# OutputJack.net
KiCad netlist of a schematic drawn in Altium Designer
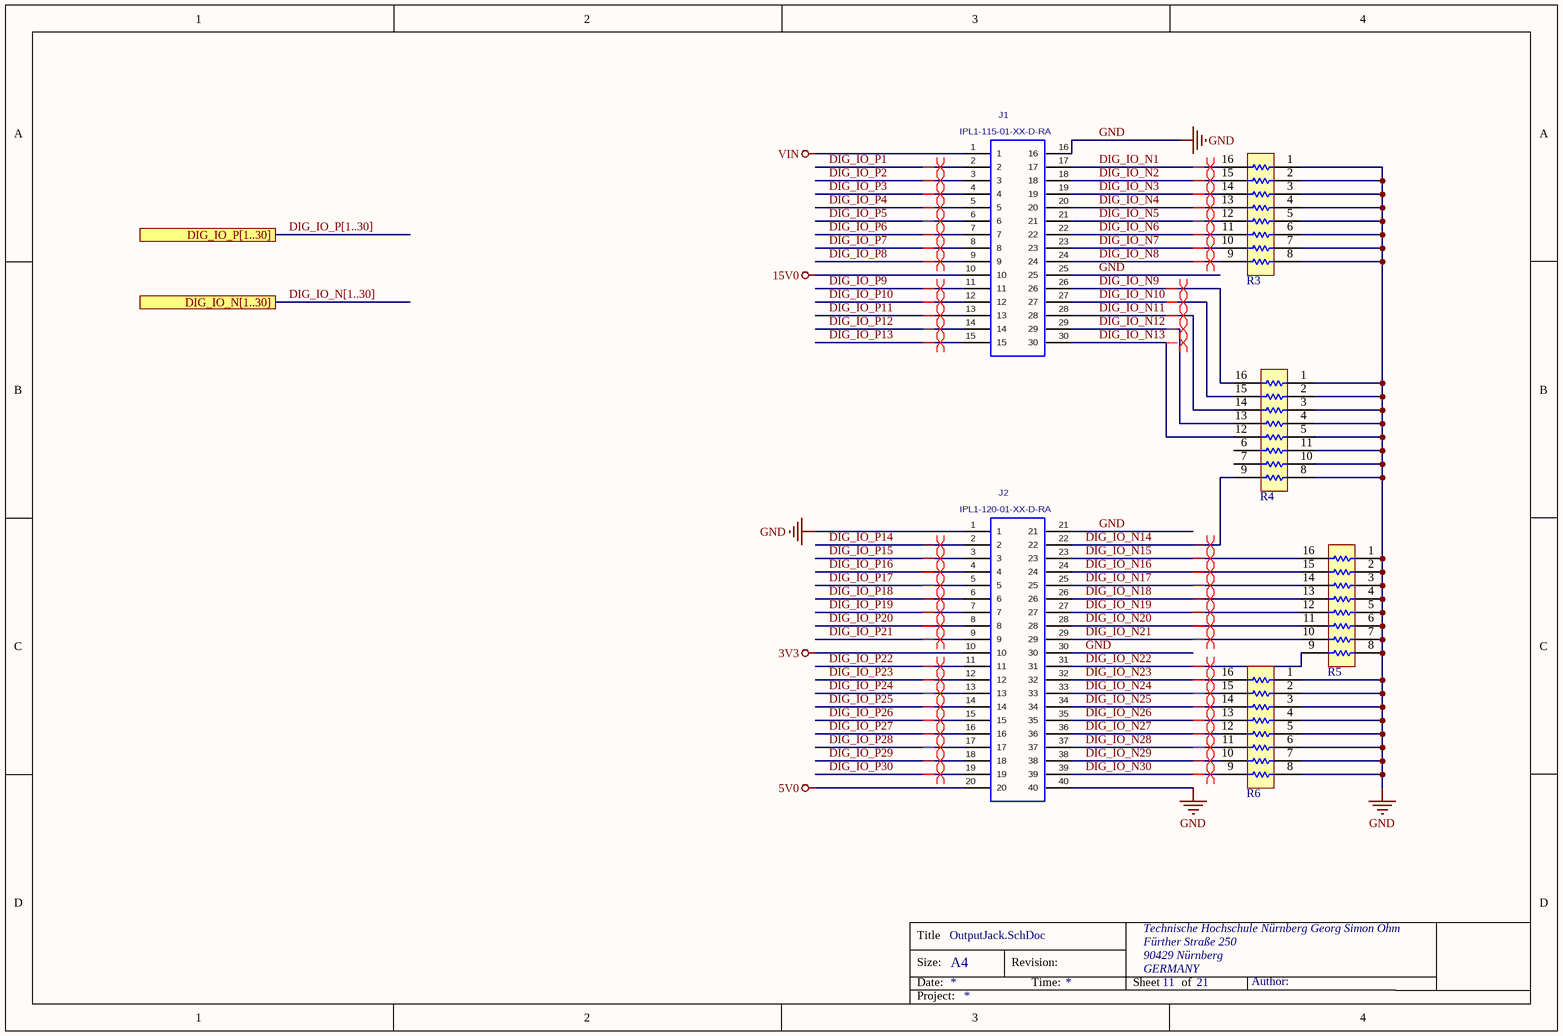
[diagram p0: OutputJack.SchDoc]

(export (version "E")
  (design (tool "Eeschema 10.0.6"))
  (components
    (comp (ref "J1")
      (value "IPL1-115-01-XX-D-RA")
      (footprint "IPL1-115-01-XX-D-RA")
      (description "Terminal Assembly, Double Row, Right Angle, Thru-Hole, 0.100\" x 0.100\" Pitch, 30 Pins.")
      (fields (field (name "CREATED") "2019-12-17_Wendy_Xin"))
      (libsource (lib "connectors") (part "IPL1-115-01-XX-D-RA"))
    )
    (comp (ref "J2")
      (value "IPL1-120-01-XX-D-RA")
      (footprint "IPL1-120-01-XX-D-RA")
      (description "Terminal Assembly, Double Row, Right Angle, Thru-Hole, 0.100\" x 0.100\" Pitch, 40 Pins.")
      (fields (field (name "CREATED") "2019-07-18_Wendy Xin"))
      (libsource (lib "connectors") (part "IPL1-120-01-XX-D-RA"))
    )
    (comp (ref "R3")
      (value "0.063W")
      (footprint "RESCAXE-50P380X160X45-16N")
      (description "Standard thick film resistor array with 8 resistors")
      (fields (field (name "CREATED") "2020-01-03_Thilo_Wendt"))
      (libsource (lib "standard_rlc") (part "8xR-Array_1_part"))
    )
    (comp (ref "R4")
      (value "0.063W")
      (footprint "RESCAXE-50P380X160X45-16N")
      (description "Standard thick film resistor array with 8 resistors")
      (fields (field (name "CREATED") "2020-01-03_Thilo_Wendt"))
      (libsource (lib "") (part "8xR-Array_1_part_1"))
    )
    (comp (ref "R5")
      (value "0.063W")
      (footprint "RESCAXE-50P380X160X45-16N")
      (description "Standard thick film resistor array with 8 resistors")
      (fields (field (name "CREATED") "2020-01-03_Thilo_Wendt"))
      (libsource (lib "standard_rlc") (part "8xR-Array_1_part"))
    )
    (comp (ref "R6")
      (value "0.063W")
      (footprint "RESCAXE-50P380X160X45-16N")
      (description "Standard thick film resistor array with 8 resistors")
      (fields (field (name "CREATED") "2020-01-03_Thilo_Wendt"))
      (libsource (lib "standard_rlc") (part "8xR-Array_1_part"))
    )
  )
  (nets
    (net (code "1") (name "/DIG_IO_N1") (class "Default")
      (node (ref "J1") (pin "17") (pinfunction "17_17") (pintype "passive"))
      (node (ref "R3") (pin "16") (pinfunction "16_16") (pintype "passive"))
    )
    (net (code "2") (name "/DIG_IO_N2") (class "Default")
      (node (ref "J1") (pin "18") (pinfunction "18_18") (pintype "passive"))
      (node (ref "R3") (pin "15") (pinfunction "15_15") (pintype "passive"))
    )
    (net (code "3") (name "/DIG_IO_N3") (class "Default")
      (node (ref "J1") (pin "19") (pinfunction "19_19") (pintype "passive"))
      (node (ref "R3") (pin "14") (pinfunction "14_14") (pintype "passive"))
    )
    (net (code "4") (name "/DIG_IO_N4") (class "Default")
      (node (ref "J1") (pin "20") (pinfunction "20_20") (pintype "passive"))
      (node (ref "R3") (pin "13") (pinfunction "13_13") (pintype "passive"))
    )
    (net (code "5") (name "/DIG_IO_N5") (class "Default")
      (node (ref "J1") (pin "21") (pinfunction "21_21") (pintype "passive"))
      (node (ref "R3") (pin "12") (pinfunction "12_12") (pintype "passive"))
    )
    (net (code "6") (name "/DIG_IO_N6") (class "Default")
      (node (ref "J1") (pin "22") (pinfunction "22_22") (pintype "passive"))
      (node (ref "R3") (pin "11") (pinfunction "11_11") (pintype "passive"))
    )
    (net (code "7") (name "/DIG_IO_N7") (class "Default")
      (node (ref "J1") (pin "23") (pinfunction "23_23") (pintype "passive"))
      (node (ref "R3") (pin "10") (pinfunction "10_10") (pintype "passive"))
    )
    (net (code "8") (name "/DIG_IO_N8") (class "Default")
      (node (ref "J1") (pin "24") (pinfunction "24_24") (pintype "passive"))
      (node (ref "R3") (pin "9") (pinfunction "9_9") (pintype "passive"))
    )
    (net (code "9") (name "/DIG_IO_N9") (class "Default")
      (node (ref "J1") (pin "26") (pinfunction "26_26") (pintype "passive"))
      (node (ref "R4") (pin "16") (pinfunction "16_16") (pintype "passive"))
    )
    (net (code "10") (name "/DIG_IO_N10") (class "Default")
      (node (ref "J1") (pin "27") (pinfunction "27_27") (pintype "passive"))
      (node (ref "R4") (pin "15") (pinfunction "15_15") (pintype "passive"))
    )
    (net (code "11") (name "/DIG_IO_N11") (class "Default")
      (node (ref "J1") (pin "28") (pinfunction "28_28") (pintype "passive"))
      (node (ref "R4") (pin "14") (pinfunction "14_14") (pintype "passive"))
    )
    (net (code "12") (name "/DIG_IO_N12") (class "Default")
      (node (ref "J1") (pin "29") (pinfunction "29_29") (pintype "passive"))
      (node (ref "R4") (pin "13") (pinfunction "13_13") (pintype "passive"))
    )
    (net (code "13") (name "/DIG_IO_N13") (class "Default")
      (node (ref "J1") (pin "30") (pinfunction "30_30") (pintype "passive"))
      (node (ref "R4") (pin "12") (pinfunction "12_12") (pintype "passive"))
    )
    (net (code "14") (name "/DIG_IO_N14") (class "Default")
      (node (ref "J2") (pin "22") (pinfunction "22_22") (pintype "passive"))
      (node (ref "R4") (pin "9") (pinfunction "9_9") (pintype "passive"))
    )
    (net (code "15") (name "/DIG_IO_N15") (class "Default")
      (node (ref "J2") (pin "23") (pinfunction "23_23") (pintype "passive"))
      (node (ref "R5") (pin "16") (pinfunction "16_16") (pintype "passive"))
    )
    (net (code "16") (name "/DIG_IO_N16") (class "Default")
      (node (ref "J2") (pin "24") (pinfunction "24_24") (pintype "passive"))
      (node (ref "R5") (pin "15") (pinfunction "15_15") (pintype "passive"))
    )
    (net (code "17") (name "/DIG_IO_N17") (class "Default")
      (node (ref "J2") (pin "25") (pinfunction "25_25") (pintype "passive"))
      (node (ref "R5") (pin "14") (pinfunction "14_14") (pintype "passive"))
    )
    (net (code "18") (name "/DIG_IO_N18") (class "Default")
      (node (ref "J2") (pin "26") (pinfunction "26_26") (pintype "passive"))
      (node (ref "R5") (pin "13") (pinfunction "13_13") (pintype "passive"))
    )
    (net (code "19") (name "/DIG_IO_N19") (class "Default")
      (node (ref "J2") (pin "27") (pinfunction "27_27") (pintype "passive"))
      (node (ref "R5") (pin "12") (pinfunction "12_12") (pintype "passive"))
    )
    (net (code "20") (name "/DIG_IO_N20") (class "Default")
      (node (ref "J2") (pin "28") (pinfunction "28_28") (pintype "passive"))
      (node (ref "R5") (pin "11") (pinfunction "11_11") (pintype "passive"))
    )
    (net (code "21") (name "/DIG_IO_N21") (class "Default")
      (node (ref "J2") (pin "29") (pinfunction "29_29") (pintype "passive"))
      (node (ref "R5") (pin "10") (pinfunction "10_10") (pintype "passive"))
    )
    (net (code "22") (name "/DIG_IO_N22") (class "Default")
      (node (ref "J2") (pin "31") (pinfunction "31_31") (pintype "passive"))
      (node (ref "R5") (pin "9") (pinfunction "9_9") (pintype "passive"))
    )
    (net (code "23") (name "/DIG_IO_N23") (class "Default")
      (node (ref "J2") (pin "32") (pinfunction "32_32") (pintype "passive"))
      (node (ref "R6") (pin "16") (pinfunction "16_16") (pintype "passive"))
    )
    (net (code "24") (name "/DIG_IO_N24") (class "Default")
      (node (ref "J2") (pin "33") (pinfunction "33_33") (pintype "passive"))
      (node (ref "R6") (pin "15") (pinfunction "15_15") (pintype "passive"))
    )
    (net (code "25") (name "/DIG_IO_N25") (class "Default")
      (node (ref "J2") (pin "34") (pinfunction "34_34") (pintype "passive"))
      (node (ref "R6") (pin "14") (pinfunction "14_14") (pintype "passive"))
    )
    (net (code "26") (name "/DIG_IO_N26") (class "Default")
      (node (ref "J2") (pin "35") (pinfunction "35_35") (pintype "passive"))
      (node (ref "R6") (pin "13") (pinfunction "13_13") (pintype "passive"))
    )
    (net (code "27") (name "/DIG_IO_N27") (class "Default")
      (node (ref "J2") (pin "36") (pinfunction "36_36") (pintype "passive"))
      (node (ref "R6") (pin "12") (pinfunction "12_12") (pintype "passive"))
    )
    (net (code "28") (name "/DIG_IO_N28") (class "Default")
      (node (ref "J2") (pin "37") (pinfunction "37_37") (pintype "passive"))
      (node (ref "R6") (pin "11") (pinfunction "11_11") (pintype "passive"))
    )
    (net (code "29") (name "/DIG_IO_N29") (class "Default")
      (node (ref "J2") (pin "38") (pinfunction "38_38") (pintype "passive"))
      (node (ref "R6") (pin "10") (pinfunction "10_10") (pintype "passive"))
    )
    (net (code "30") (name "/DIG_IO_N30") (class "Default")
      (node (ref "J2") (pin "39") (pinfunction "39_39") (pintype "passive"))
      (node (ref "R6") (pin "9") (pinfunction "9_9") (pintype "passive"))
    )
    (net (code "32") (name "/DIG_IO_P1") (class "Default")
      (node (ref "J1") (pin "2") (pinfunction "2_2") (pintype "passive"))
    )
    (net (code "33") (name "/DIG_IO_P2") (class "Default")
      (node (ref "J1") (pin "3") (pinfunction "3_3") (pintype "passive"))
    )
    (net (code "34") (name "/DIG_IO_P3") (class "Default")
      (node (ref "J1") (pin "4") (pinfunction "4_4") (pintype "passive"))
    )
    (net (code "35") (name "/DIG_IO_P4") (class "Default")
      (node (ref "J1") (pin "5") (pinfunction "5_5") (pintype "passive"))
    )
    (net (code "36") (name "/DIG_IO_P5") (class "Default")
      (node (ref "J1") (pin "6") (pinfunction "6_6") (pintype "passive"))
    )
    (net (code "37") (name "/DIG_IO_P6") (class "Default")
      (node (ref "J1") (pin "7") (pinfunction "7_7") (pintype "passive"))
    )
    (net (code "38") (name "/DIG_IO_P7") (class "Default")
      (node (ref "J1") (pin "8") (pinfunction "8_8") (pintype "passive"))
    )
    (net (code "39") (name "/DIG_IO_P8") (class "Default")
      (node (ref "J1") (pin "9") (pinfunction "9_9") (pintype "passive"))
    )
    (net (code "40") (name "/DIG_IO_P9") (class "Default")
      (node (ref "J1") (pin "11") (pinfunction "11_11") (pintype "passive"))
    )
    (net (code "41") (name "/DIG_IO_P10") (class "Default")
      (node (ref "J1") (pin "12") (pinfunction "12_12") (pintype "passive"))
    )
    (net (code "42") (name "/DIG_IO_P11") (class "Default")
      (node (ref "J1") (pin "13") (pinfunction "13_13") (pintype "passive"))
    )
    (net (code "43") (name "/DIG_IO_P12") (class "Default")
      (node (ref "J1") (pin "14") (pinfunction "14_14") (pintype "passive"))
    )
    (net (code "44") (name "/DIG_IO_P13") (class "Default")
      (node (ref "J1") (pin "15") (pinfunction "15_15") (pintype "passive"))
    )
    (net (code "45") (name "/DIG_IO_P14") (class "Default")
      (node (ref "J2") (pin "2") (pinfunction "2_2") (pintype "passive"))
    )
    (net (code "46") (name "/DIG_IO_P15") (class "Default")
      (node (ref "J2") (pin "3") (pinfunction "3_3") (pintype "passive"))
    )
    (net (code "47") (name "/DIG_IO_P16") (class "Default")
      (node (ref "J2") (pin "4") (pinfunction "4_4") (pintype "passive"))
    )
    (net (code "48") (name "/DIG_IO_P17") (class "Default")
      (node (ref "J2") (pin "5") (pinfunction "5_5") (pintype "passive"))
    )
    (net (code "49") (name "/DIG_IO_P18") (class "Default")
      (node (ref "J2") (pin "6") (pinfunction "6_6") (pintype "passive"))
    )
    (net (code "50") (name "/DIG_IO_P19") (class "Default")
      (node (ref "J2") (pin "7") (pinfunction "7_7") (pintype "passive"))
    )
    (net (code "51") (name "/DIG_IO_P20") (class "Default")
      (node (ref "J2") (pin "8") (pinfunction "8_8") (pintype "passive"))
    )
    (net (code "52") (name "/DIG_IO_P21") (class "Default")
      (node (ref "J2") (pin "9") (pinfunction "9_9") (pintype "passive"))
    )
    (net (code "53") (name "/DIG_IO_P22") (class "Default")
      (node (ref "J2") (pin "11") (pinfunction "11_11") (pintype "passive"))
    )
    (net (code "54") (name "/DIG_IO_P23") (class "Default")
      (node (ref "J2") (pin "12") (pinfunction "12_12") (pintype "passive"))
    )
    (net (code "55") (name "/DIG_IO_P24") (class "Default")
      (node (ref "J2") (pin "13") (pinfunction "13_13") (pintype "passive"))
    )
    (net (code "56") (name "/DIG_IO_P25") (class "Default")
      (node (ref "J2") (pin "14") (pinfunction "14_14") (pintype "passive"))
    )
    (net (code "57") (name "/DIG_IO_P26") (class "Default")
      (node (ref "J2") (pin "15") (pinfunction "15_15") (pintype "passive"))
    )
    (net (code "58") (name "/DIG_IO_P27") (class "Default")
      (node (ref "J2") (pin "16") (pinfunction "16_16") (pintype "passive"))
    )
    (net (code "59") (name "/DIG_IO_P28") (class "Default")
      (node (ref "J2") (pin "17") (pinfunction "17_17") (pintype "passive"))
    )
    (net (code "60") (name "/DIG_IO_P29") (class "Default")
      (node (ref "J2") (pin "18") (pinfunction "18_18") (pintype "passive"))
    )
    (net (code "61") (name "/DIG_IO_P30") (class "Default")
      (node (ref "J2") (pin "19") (pinfunction "19_19") (pintype "passive"))
    )
    (net (code "63") (name "3V3") (class "Default")
      (node (ref "J2") (pin "10") (pinfunction "10_10") (pintype "passive"))
    )
    (net (code "64") (name "5V0") (class "Default")
      (node (ref "J2") (pin "20") (pinfunction "20_20") (pintype "passive"))
    )
    (net (code "65") (name "15V0") (class "Default")
      (node (ref "J1") (pin "10") (pinfunction "10_10") (pintype "passive"))
    )
    (net (code "66") (name "GND") (class "Default")
      (node (ref "J1") (pin "16") (pinfunction "16_16") (pintype "passive"))
      (node (ref "J1") (pin "25") (pinfunction "25_25") (pintype "passive"))
      (node (ref "J2") (pin "1") (pinfunction "1_1") (pintype "passive"))
      (node (ref "J2") (pin "21") (pinfunction "21_21") (pintype "passive"))
      (node (ref "J2") (pin "30") (pinfunction "30_30") (pintype "passive"))
      (node (ref "J2") (pin "40") (pinfunction "40_40") (pintype "passive"))
      (node (ref "R3") (pin "1") (pinfunction "1_1") (pintype "passive"))
      (node (ref "R3") (pin "2") (pinfunction "2_2") (pintype "passive"))
      (node (ref "R3") (pin "3") (pinfunction "3_3") (pintype "passive"))
      (node (ref "R3") (pin "4") (pinfunction "4_4") (pintype "passive"))
      (node (ref "R3") (pin "5") (pinfunction "5_5") (pintype "passive"))
      (node (ref "R3") (pin "6") (pinfunction "6_6") (pintype "passive"))
      (node (ref "R3") (pin "7") (pinfunction "7_7") (pintype "passive"))
      (node (ref "R3") (pin "8") (pinfunction "8_8") (pintype "passive"))
      (node (ref "R4") (pin "1") (pinfunction "1_1") (pintype "passive"))
      (node (ref "R4") (pin "10") (pinfunction "10_10") (pintype "passive"))
      (node (ref "R4") (pin "11") (pinfunction "11_11") (pintype "passive"))
      (node (ref "R4") (pin "2") (pinfunction "2_2") (pintype "passive"))
      (node (ref "R4") (pin "3") (pinfunction "3_3") (pintype "passive"))
      (node (ref "R4") (pin "4") (pinfunction "4_4") (pintype "passive"))
      (node (ref "R4") (pin "5") (pinfunction "5_5") (pintype "passive"))
      (node (ref "R4") (pin "8") (pinfunction "8_8") (pintype "passive"))
      (node (ref "R5") (pin "1") (pinfunction "1_1") (pintype "passive"))
      (node (ref "R5") (pin "2") (pinfunction "2_2") (pintype "passive"))
      (node (ref "R5") (pin "3") (pinfunction "3_3") (pintype "passive"))
      (node (ref "R5") (pin "4") (pinfunction "4_4") (pintype "passive"))
      (node (ref "R5") (pin "5") (pinfunction "5_5") (pintype "passive"))
      (node (ref "R5") (pin "6") (pinfunction "6_6") (pintype "passive"))
      (node (ref "R5") (pin "7") (pinfunction "7_7") (pintype "passive"))
      (node (ref "R5") (pin "8") (pinfunction "8_8") (pintype "passive"))
      (node (ref "R6") (pin "1") (pinfunction "1_1") (pintype "passive"))
      (node (ref "R6") (pin "2") (pinfunction "2_2") (pintype "passive"))
      (node (ref "R6") (pin "3") (pinfunction "3_3") (pintype "passive"))
      (node (ref "R6") (pin "4") (pinfunction "4_4") (pintype "passive"))
      (node (ref "R6") (pin "5") (pinfunction "5_5") (pintype "passive"))
      (node (ref "R6") (pin "6") (pinfunction "6_6") (pintype "passive"))
      (node (ref "R6") (pin "7") (pinfunction "7_7") (pintype "passive"))
      (node (ref "R6") (pin "8") (pinfunction "8_8") (pintype "passive"))
    )
    (net (code "67") (name "VIN") (class "Default")
      (node (ref "J1") (pin "1") (pinfunction "1_1") (pintype "passive"))
    )
    (net (code "68") (name "unconnected-(R4-Pad6)") (class "Default")
      (node (ref "R4") (pin "6") (pinfunction "6_6") (pintype "passive"))
    )
    (net (code "69") (name "unconnected-(R4-Pad7)") (class "Default")
      (node (ref "R4") (pin "7") (pinfunction "7_7") (pintype "passive"))
    )
  )
)
